# SignalCircuit.net
KiCad netlist of a schematic drawn in Altium Designer
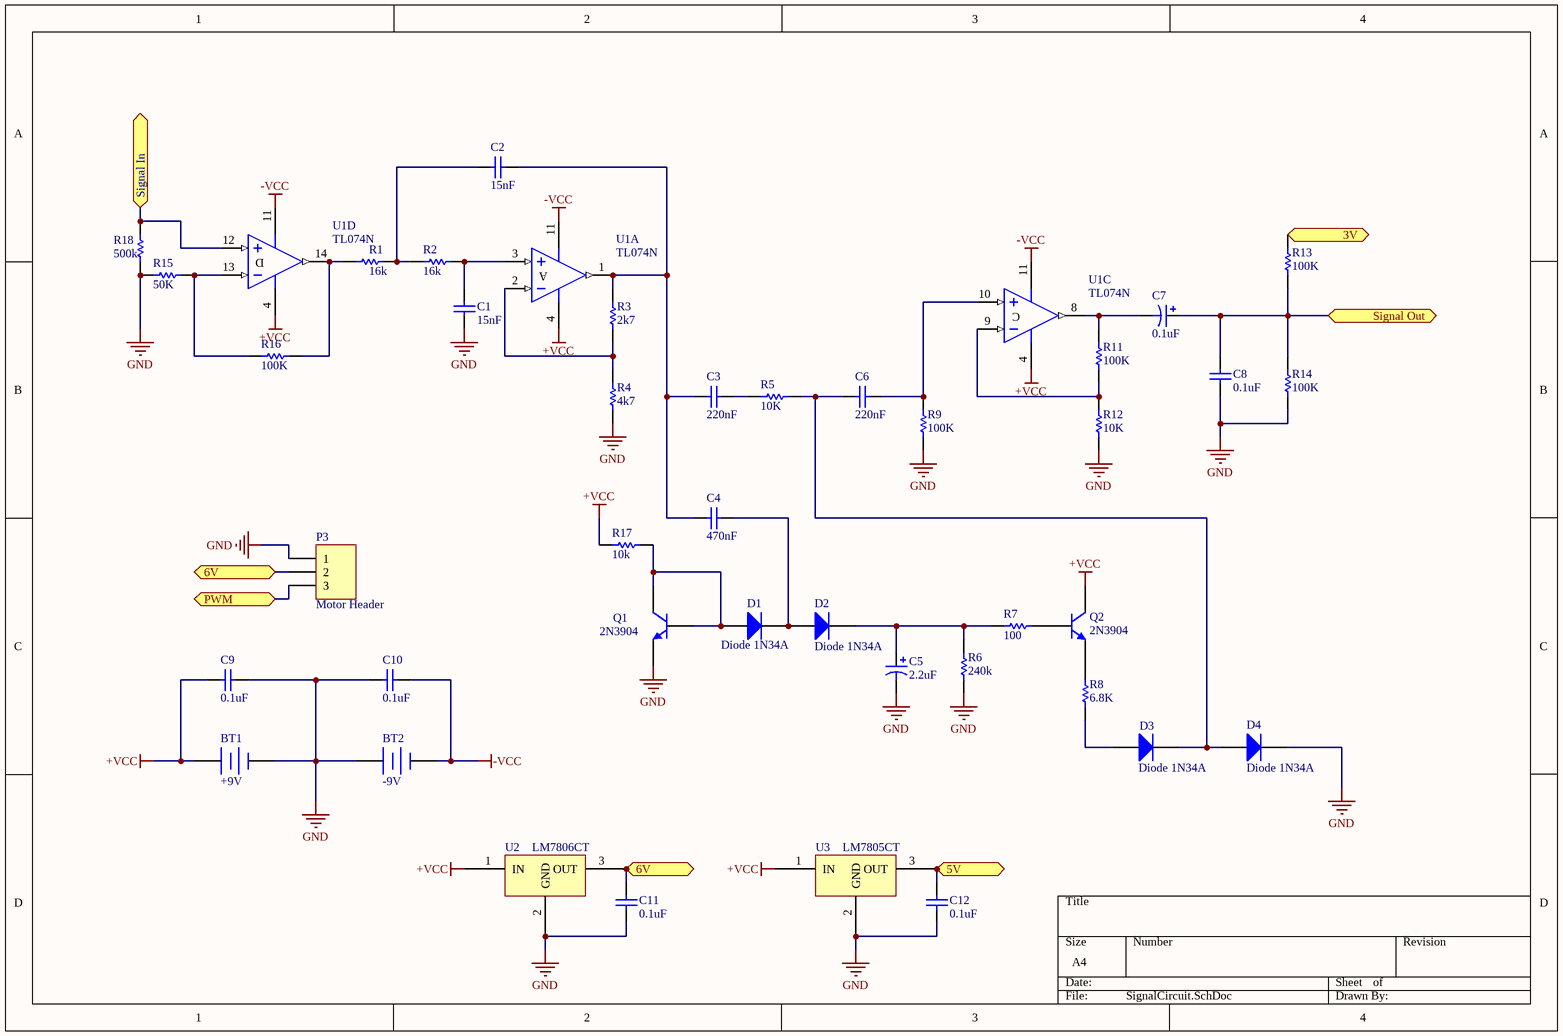
[diagram p0: SignalCircuit.SchDoc]

(export (version "E")
  (design (tool "Eeschema 10.0.6"))
  (components
    (comp (ref "BT1")
      (value "+9V")
      (footprint "BAT-2")
      (description "Multicell Battery")
      (fields (field (name "PUBLISHER") "Altium Limited"))
      (libsource (lib "Miscellaneous Devices") (part "Battery"))
    )
    (comp (ref "BT2")
      (value "-9V")
      (footprint "BAT-2")
      (description "Multicell Battery")
      (fields (field (name "PUBLISHER") "Altium Limited"))
      (libsource (lib "Miscellaneous Devices") (part "Battery"))
    )
    (comp (ref "C1")
      (value "15nF")
      (footprint "RAD-0.3")
      (description "Capacitor")
      (fields (field (name "PUBLISHER") "Altium Limited"))
      (libsource (lib "Miscellaneous Devices") (part "Cap"))
    )
    (comp (ref "C2")
      (value "15nF")
      (footprint "RAD-0.3")
      (description "Capacitor")
      (fields (field (name "PUBLISHER") "Altium Limited"))
      (libsource (lib "Miscellaneous Devices") (part "Cap"))
    )
    (comp (ref "C3")
      (value "220nF")
      (footprint "RAD-0.3")
      (description "Capacitor")
      (fields (field (name "PUBLISHER") "Altium Limited"))
      (libsource (lib "Miscellaneous Devices") (part "Cap"))
    )
    (comp (ref "C4")
      (value "470nF")
      (footprint "RAD-0.3")
      (description "Capacitor")
      (fields (field (name "PUBLISHER") "Altium Limited"))
      (libsource (lib "Miscellaneous Devices") (part "Cap"))
    )
    (comp (ref "C5")
      (value "2.2uF")
      (footprint "RAD0.2-POL")
      (description "Polarized Capacitor (Radial)")
      (fields (field (name "PUBLISHER") "Altium Limited"))
      (libsource (lib "") (part "Cap Pol1_1"))
    )
    (comp (ref "C6")
      (value "220nF")
      (footprint "RAD-0.3")
      (description "Capacitor")
      (fields (field (name "PUBLISHER") "Altium Limited"))
      (libsource (lib "Miscellaneous Devices") (part "Cap"))
    )
    (comp (ref "C7")
      (value "0.1uF")
      (footprint "RAD0.2-POL")
      (description "Polarized Capacitor (Radial)")
      (fields (field (name "PUBLISHER") "Altium Limited"))
      (libsource (lib "Miscellaneous Devices") (part "Cap Pol1"))
    )
    (comp (ref "C8")
      (value "0.1uF")
      (footprint "RAD-0.3")
      (description "Capacitor")
      (fields (field (name "PUBLISHER") "Altium Limited"))
      (libsource (lib "Miscellaneous Devices") (part "Cap"))
    )
    (comp (ref "C9")
      (value "0.1uF")
      (footprint "RAD-0.3")
      (description "Capacitor")
      (fields (field (name "PUBLISHER") "Altium Limited"))
      (libsource (lib "Miscellaneous Devices") (part "Cap"))
    )
    (comp (ref "C10")
      (value "0.1uF")
      (footprint "RAD-0.3")
      (description "Capacitor")
      (fields (field (name "PUBLISHER") "Altium Limited"))
      (libsource (lib "Miscellaneous Devices") (part "Cap"))
    )
    (comp (ref "C11")
      (value "0.1uF")
      (footprint "RAD-0.3")
      (description "Capacitor")
      (fields (field (name "PUBLISHER") "Altium Limited"))
      (libsource (lib "Miscellaneous Devices") (part "Cap"))
    )
    (comp (ref "C12")
      (value "0.1uF")
      (footprint "RAD-0.3")
      (description "Capacitor")
      (fields (field (name "PUBLISHER") "Altium Limited"))
      (libsource (lib "Miscellaneous Devices") (part "Cap"))
    )
    (comp (ref "D1")
      (value "Diode 1N34A")
      (footprint "DO-35")
      (description "High Conductance Fast Diode")
      (fields (field (name "PUBLISHER") "Altium Limited"))
      (libsource (lib "Miscellaneous Devices") (part "Diode 1N914"))
    )
    (comp (ref "D2")
      (value "Diode 1N34A")
      (footprint "DO-35")
      (description "High Conductance Fast Diode")
      (fields (field (name "PUBLISHER") "Altium Limited"))
      (libsource (lib "Miscellaneous Devices") (part "Diode 1N914"))
    )
    (comp (ref "D3")
      (value "Diode 1N34A")
      (footprint "DO-35")
      (description "High Conductance Fast Diode")
      (fields (field (name "PUBLISHER") "Altium Limited"))
      (libsource (lib "Miscellaneous Devices") (part "Diode 1N914"))
    )
    (comp (ref "D4")
      (value "Diode 1N34A")
      (footprint "DO-35")
      (description "High Conductance Fast Diode")
      (fields (field (name "PUBLISHER") "Altium Limited"))
      (libsource (lib "Miscellaneous Devices") (part "Diode 1N914"))
    )
    (comp (ref "P3")
      (value "Motor Header")
      (footprint "HDR1X3")
      (description "Header, 3-Pin")
      (fields (field (name "PUBLISHER") "Altium Limited"))
      (libsource (lib "Miscellaneous Connectors") (part "Header 3"))
    )
    (comp (ref "Q1")
      (value "2N3904")
      (footprint "TO-226AE")
      (description "NPN General Purpose Amplifier")
      (fields (field (name "PUBLISHER") "Altium Limited"))
      (libsource (lib "Miscellaneous Devices") (part "2N3904"))
    )
    (comp (ref "Q2")
      (value "2N3904")
      (footprint "TO-226AE")
      (description "NPN General Purpose Amplifier")
      (fields (field (name "PUBLISHER") "Altium Limited"))
      (libsource (lib "Miscellaneous Devices") (part "2N3904"))
    )
    (comp (ref "R1")
      (value "16k")
      (footprint "AXIAL-0.3")
      (description "Resistor")
      (fields (field (name "PUBLISHER") "Altium Limited"))
      (libsource (lib "Miscellaneous Devices") (part "Res1"))
    )
    (comp (ref "R2")
      (value "16k")
      (footprint "AXIAL-0.3")
      (description "Resistor")
      (fields (field (name "PUBLISHER") "Altium Limited"))
      (libsource (lib "Miscellaneous Devices") (part "Res1"))
    )
    (comp (ref "R3")
      (value "2k7")
      (footprint "AXIAL-0.3")
      (description "Resistor")
      (fields (field (name "PUBLISHER") "Altium Limited"))
      (libsource (lib "Miscellaneous Devices") (part "Res1"))
    )
    (comp (ref "R4")
      (value "4k7")
      (footprint "AXIAL-0.3")
      (description "Resistor")
      (fields (field (name "PUBLISHER") "Altium Limited"))
      (libsource (lib "Miscellaneous Devices") (part "Res1"))
    )
    (comp (ref "R5")
      (value "10K")
      (footprint "AXIAL-0.3")
      (description "Resistor")
      (fields (field (name "PUBLISHER") "Altium Limited"))
      (libsource (lib "Miscellaneous Devices") (part "Res1"))
    )
    (comp (ref "R6")
      (value "240k")
      (footprint "AXIAL-0.3")
      (description "Resistor")
      (fields (field (name "PUBLISHER") "Altium Limited"))
      (libsource (lib "Miscellaneous Devices") (part "Res1"))
    )
    (comp (ref "R7")
      (value "100")
      (footprint "AXIAL-0.3")
      (description "Resistor")
      (fields (field (name "PUBLISHER") "Altium Limited"))
      (libsource (lib "Miscellaneous Devices") (part "Res1"))
    )
    (comp (ref "R8")
      (value "6.8K")
      (footprint "AXIAL-0.3")
      (description "Resistor")
      (fields (field (name "PUBLISHER") "Altium Limited"))
      (libsource (lib "Miscellaneous Devices") (part "Res1"))
    )
    (comp (ref "R9")
      (value "100K")
      (footprint "AXIAL-0.3")
      (description "Resistor")
      (fields (field (name "PUBLISHER") "Altium Limited"))
      (libsource (lib "Miscellaneous Devices") (part "Res1"))
    )
    (comp (ref "R11")
      (value "100K")
      (footprint "AXIAL-0.3")
      (description "Resistor")
      (fields (field (name "PUBLISHER") "Altium Limited"))
      (libsource (lib "Miscellaneous Devices") (part "Res1"))
    )
    (comp (ref "R12")
      (value "10K")
      (footprint "AXIAL-0.3")
      (description "Resistor")
      (fields (field (name "PUBLISHER") "Altium Limited"))
      (libsource (lib "Miscellaneous Devices") (part "Res1"))
    )
    (comp (ref "R13")
      (value "100K")
      (footprint "AXIAL-0.3")
      (description "Resistor")
      (fields (field (name "PUBLISHER") "Altium Limited"))
      (libsource (lib "Miscellaneous Devices") (part "Res1"))
    )
    (comp (ref "R14")
      (value "100K")
      (footprint "AXIAL-0.3")
      (description "Resistor")
      (fields (field (name "PUBLISHER") "Altium Limited"))
      (libsource (lib "Miscellaneous Devices") (part "Res1"))
    )
    (comp (ref "R15")
      (value "50K")
      (footprint "AXIAL-0.3")
      (description "Resistor")
      (fields (field (name "PUBLISHER") "Altium Limited"))
      (libsource (lib "Miscellaneous Devices") (part "Res1"))
    )
    (comp (ref "R16")
      (value "100K")
      (footprint "AXIAL-0.3")
      (description "Resistor")
      (fields (field (name "PUBLISHER") "Altium Limited"))
      (libsource (lib "Miscellaneous Devices") (part "Res1"))
    )
    (comp (ref "R17")
      (value "10k")
      (footprint "AXIAL-0.3")
      (description "Resistor")
      (fields (field (name "PUBLISHER") "Altium Limited"))
      (libsource (lib "Miscellaneous Devices") (part "Res1"))
    )
    (comp (ref "R18")
      (value "500k")
      (footprint "AXIAL-0.3")
      (description "Resistor")
      (fields (field (name "PUBLISHER") "Altium Limited"))
      (libsource (lib "Miscellaneous Devices") (part "Res1"))
    )
    (comp (ref "U1")
      (value "TL074N")
      (footprint "N014")
      (description "Low-Noise JFET-Input Operational Amplifier")
      (fields (field (name "PUBLISHER") "Altium Limited"))
      (libsource (lib "TI Operational Amplifier") (part "TL074N"))
    )
    (comp (ref "U2")
      (value "LM7806CT")
      (footprint "TO-220")
      (description "Three Terminal Voltage Regulator")
      (libsource (lib "ELEX130") (part "LM7805CT(3)"))
    )
    (comp (ref "U3")
      (value "LM7805CT")
      (footprint "TO-220")
      (description "Three Terminal Voltage Regulator")
      (libsource (lib "ELEX130") (part "LM7805CT(3)"))
    )
  )
  (nets
    (net (code "1") (name "+VCC") (class "Default")
      (node (ref "BT1") (pin "1") (pinfunction "+_1") (pintype "passive"))
      (node (ref "C9") (pin "1") (pinfunction "1_1") (pintype "passive"))
      (node (ref "Q2") (pin "3") (pinfunction "C_3") (pintype "passive"))
      (node (ref "R17") (pin "2") (pinfunction "2_2") (pintype "passive"))
      (node (ref "U1") (pin "4") (pinfunction "V+_4") (pintype "power_in"))
      (node (ref "U2") (pin "1") (pinfunction "IN_1") (pintype "power_in"))
      (node (ref "U3") (pin "1") (pinfunction "IN_1") (pintype "power_in"))
    )
    (net (code "2") (name "-VCC") (class "Default")
      (node (ref "BT2") (pin "2") (pinfunction "-_2") (pintype "passive"))
      (node (ref "C10") (pin "2") (pinfunction "2_2") (pintype "passive"))
      (node (ref "U1") (pin "11") (pinfunction "V-_11") (pintype "power_in"))
    )
    (net (code "3") (name "/3V") (class "Default")
      (node (ref "R13") (pin "2") (pinfunction "2_2") (pintype "passive"))
    )
    (net (code "4") (name "/5V") (class "Default")
      (node (ref "C12") (pin "2") (pinfunction "2_2") (pintype "passive"))
      (node (ref "U3") (pin "3") (pinfunction "OUT_3") (pintype "power_in"))
    )
    (net (code "5") (name "/6V") (class "Default")
      (node (ref "C11") (pin "2") (pinfunction "2_2") (pintype "passive"))
      (node (ref "P3") (pin "2") (pinfunction "2_2") (pintype "passive"))
      (node (ref "U2") (pin "3") (pinfunction "OUT_3") (pintype "power_in"))
    )
    (net (code "6") (name "/PWM") (class "Default")
      (node (ref "P3") (pin "3") (pinfunction "3_3") (pintype "passive"))
    )
    (net (code "7") (name "/Signal In") (class "Default")
      (node (ref "R18") (pin "2") (pinfunction "2_2") (pintype "passive"))
      (node (ref "U1") (pin "12") (pinfunction "IN+_12") (pintype "input"))
    )
    (net (code "8") (name "/Signal Out") (class "Default")
      (node (ref "C7") (pin "1") (pinfunction "1_1") (pintype "passive"))
      (node (ref "C8") (pin "1") (pinfunction "1_1") (pintype "passive"))
      (node (ref "R13") (pin "1") (pinfunction "1_1") (pintype "passive"))
      (node (ref "R14") (pin "2") (pinfunction "2_2") (pintype "passive"))
    )
    (net (code "9") (name "GND") (class "Default")
      (node (ref "BT1") (pin "2") (pinfunction "-_2") (pintype "passive"))
      (node (ref "BT2") (pin "1") (pinfunction "+_1") (pintype "passive"))
      (node (ref "C1") (pin "1") (pinfunction "1_1") (pintype "passive"))
      (node (ref "C10") (pin "1") (pinfunction "1_1") (pintype "passive"))
      (node (ref "C11") (pin "1") (pinfunction "1_1") (pintype "passive"))
      (node (ref "C12") (pin "1") (pinfunction "1_1") (pintype "passive"))
      (node (ref "C5") (pin "2") (pinfunction "2_2") (pintype "passive"))
      (node (ref "C8") (pin "2") (pinfunction "2_2") (pintype "passive"))
      (node (ref "C9") (pin "2") (pinfunction "2_2") (pintype "passive"))
      (node (ref "D4") (pin "2") (pinfunction "K_2") (pintype "passive"))
      (node (ref "P3") (pin "1") (pinfunction "1_1") (pintype "passive"))
      (node (ref "Q1") (pin "1") (pinfunction "E_1") (pintype "passive"))
      (node (ref "R12") (pin "1") (pinfunction "1_1") (pintype "passive"))
      (node (ref "R14") (pin "1") (pinfunction "1_1") (pintype "passive"))
      (node (ref "R15") (pin "2") (pinfunction "2_2") (pintype "passive"))
      (node (ref "R18") (pin "1") (pinfunction "1_1") (pintype "passive"))
      (node (ref "R4") (pin "1") (pinfunction "1_1") (pintype "passive"))
      (node (ref "R6") (pin "1") (pinfunction "1_1") (pintype "passive"))
      (node (ref "R9") (pin "1") (pinfunction "1_1") (pintype "passive"))
      (node (ref "U2") (pin "2") (pinfunction "GND_2") (pintype "power_in"))
      (node (ref "U3") (pin "2") (pinfunction "GND_2") (pintype "power_in"))
    )
    (net (code "10") (name "Net-(C2-Pad1)") (class "Default")
      (node (ref "C2") (pin "1") (pinfunction "1_1") (pintype "passive"))
      (node (ref "R1") (pin "2") (pinfunction "2_2") (pintype "passive"))
      (node (ref "R2") (pin "1") (pinfunction "1_1") (pintype "passive"))
    )
    (net (code "11") (name "Net-(C3-Pad2)") (class "Default")
      (node (ref "C3") (pin "2") (pinfunction "2_2") (pintype "passive"))
      (node (ref "R5") (pin "1") (pinfunction "1_1") (pintype "passive"))
    )
    (net (code "12") (name "Net-(D1-A)") (class "Default")
      (node (ref "D1") (pin "1") (pinfunction "A_1") (pintype "passive"))
      (node (ref "Q1") (pin "2") (pinfunction "B_2") (pintype "passive"))
      (node (ref "Q1") (pin "3") (pinfunction "C_3") (pintype "passive"))
      (node (ref "R17") (pin "1") (pinfunction "1_1") (pintype "passive"))
    )
    (net (code "13") (name "Net-(D1-K)") (class "Default")
      (node (ref "C4") (pin "2") (pinfunction "2_2") (pintype "passive"))
      (node (ref "D1") (pin "2") (pinfunction "K_2") (pintype "passive"))
      (node (ref "D2") (pin "1") (pinfunction "A_1") (pintype "passive"))
    )
    (net (code "14") (name "Net-(D2-K)") (class "Default")
      (node (ref "C5") (pin "1") (pinfunction "1_1") (pintype "passive"))
      (node (ref "D2") (pin "2") (pinfunction "K_2") (pintype "passive"))
      (node (ref "R6") (pin "2") (pinfunction "2_2") (pintype "passive"))
      (node (ref "R7") (pin "1") (pinfunction "1_1") (pintype "passive"))
    )
    (net (code "15") (name "Net-(D3-A)") (class "Default")
      (node (ref "D3") (pin "1") (pinfunction "A_1") (pintype "passive"))
      (node (ref "R8") (pin "1") (pinfunction "1_1") (pintype "passive"))
    )
    (net (code "16") (name "Net-(D3-K)") (class "Default")
      (node (ref "C6") (pin "1") (pinfunction "1_1") (pintype "passive"))
      (node (ref "D3") (pin "2") (pinfunction "K_2") (pintype "passive"))
      (node (ref "D4") (pin "1") (pinfunction "A_1") (pintype "passive"))
      (node (ref "R5") (pin "2") (pinfunction "2_2") (pintype "passive"))
    )
    (net (code "17") (name "Net-(Q2-B)") (class "Default")
      (node (ref "Q2") (pin "2") (pinfunction "B_2") (pintype "passive"))
      (node (ref "R7") (pin "2") (pinfunction "2_2") (pintype "passive"))
    )
    (net (code "18") (name "Net-(Q2-E)") (class "Default")
      (node (ref "Q2") (pin "1") (pinfunction "E_1") (pintype "passive"))
      (node (ref "R8") (pin "2") (pinfunction "2_2") (pintype "passive"))
    )
    (net (code "19") (name "Net-(U1A-IN+)") (class "Default")
      (node (ref "C1") (pin "2") (pinfunction "2_2") (pintype "passive"))
      (node (ref "R2") (pin "2") (pinfunction "2_2") (pintype "passive"))
      (node (ref "U1") (pin "3") (pinfunction "IN+_3") (pintype "input"))
    )
    (net (code "20") (name "Net-(U1A-IN-)") (class "Default")
      (node (ref "R3") (pin "1") (pinfunction "1_1") (pintype "passive"))
      (node (ref "R4") (pin "2") (pinfunction "2_2") (pintype "passive"))
      (node (ref "U1") (pin "2") (pinfunction "IN-_2") (pintype "input"))
    )
    (net (code "21") (name "Net-(U1A-OUT)") (class "Default")
      (node (ref "C2") (pin "2") (pinfunction "2_2") (pintype "passive"))
      (node (ref "C3") (pin "1") (pinfunction "1_1") (pintype "passive"))
      (node (ref "C4") (pin "1") (pinfunction "1_1") (pintype "passive"))
      (node (ref "R3") (pin "2") (pinfunction "2_2") (pintype "passive"))
      (node (ref "U1") (pin "1") (pinfunction "OUT_1") (pintype "output"))
    )
    (net (code "22") (name "Net-(U1C-IN+)") (class "Default")
      (node (ref "C6") (pin "2") (pinfunction "2_2") (pintype "passive"))
      (node (ref "R9") (pin "2") (pinfunction "2_2") (pintype "passive"))
      (node (ref "U1") (pin "10") (pinfunction "IN+_10") (pintype "input"))
    )
    (net (code "23") (name "Net-(U1C-IN-)") (class "Default")
      (node (ref "R11") (pin "1") (pinfunction "1_1") (pintype "passive"))
      (node (ref "R12") (pin "2") (pinfunction "2_2") (pintype "passive"))
      (node (ref "U1") (pin "9") (pinfunction "IN-_9") (pintype "input"))
    )
    (net (code "24") (name "Net-(U1C-OUT)") (class "Default")
      (node (ref "C7") (pin "2") (pinfunction "2_2") (pintype "passive"))
      (node (ref "R11") (pin "2") (pinfunction "2_2") (pintype "passive"))
      (node (ref "U1") (pin "8") (pinfunction "OUT_8") (pintype "output"))
    )
    (net (code "25") (name "Net-(U1D-IN-)") (class "Default")
      (node (ref "R15") (pin "1") (pinfunction "1_1") (pintype "passive"))
      (node (ref "R16") (pin "2") (pinfunction "2_2") (pintype "passive"))
      (node (ref "U1") (pin "13") (pinfunction "IN-_13") (pintype "input"))
    )
    (net (code "26") (name "Net-(U1D-OUT)") (class "Default")
      (node (ref "R1") (pin "1") (pinfunction "1_1") (pintype "passive"))
      (node (ref "R16") (pin "1") (pinfunction "1_1") (pintype "passive"))
      (node (ref "U1") (pin "14") (pinfunction "OUT_14") (pintype "output"))
    )
  )
)
